# 02_MonitorStage_v1.net
KiCad netlist of a schematic drawn in EAGLE
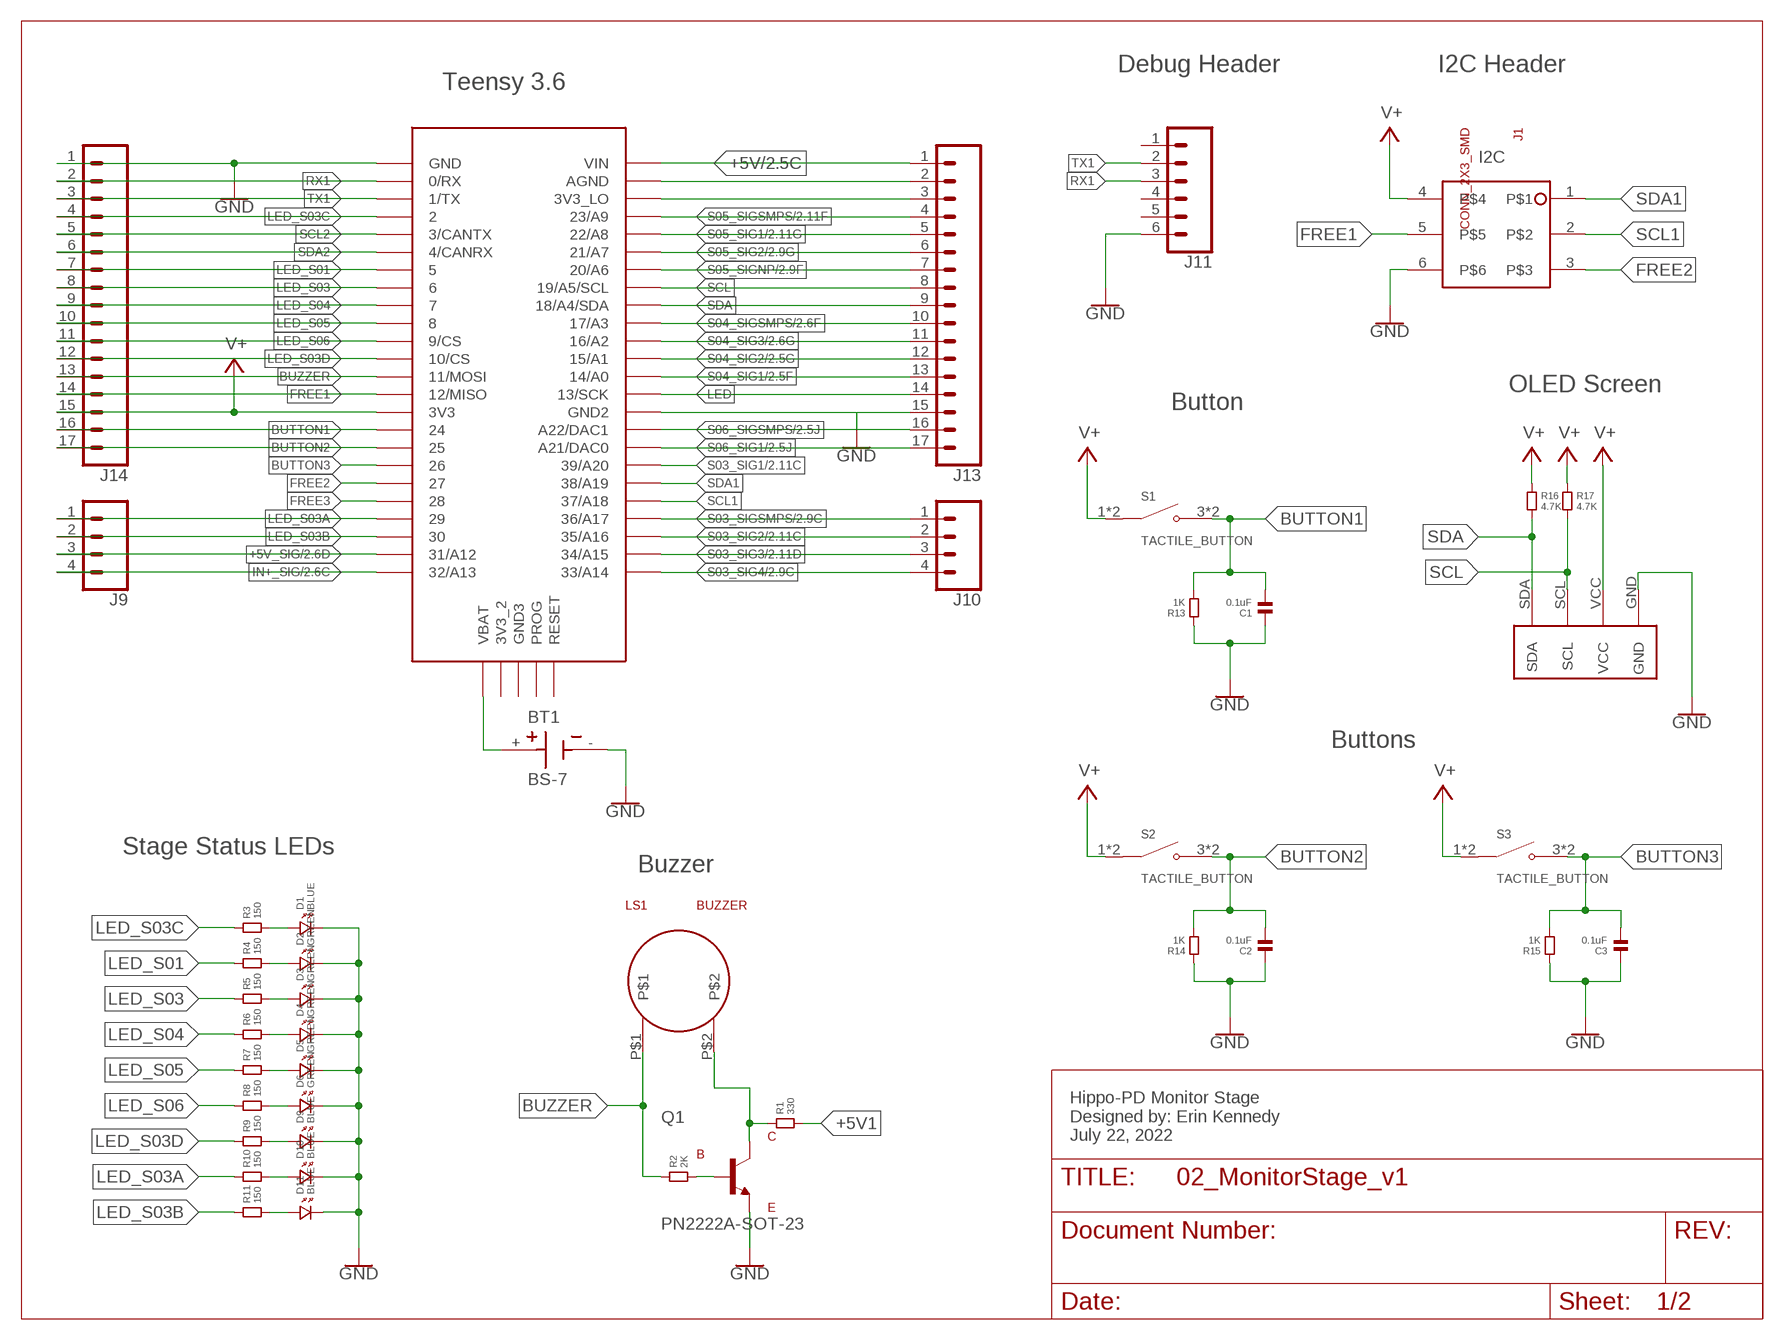
[diagram p0: schematic, sheet 1]
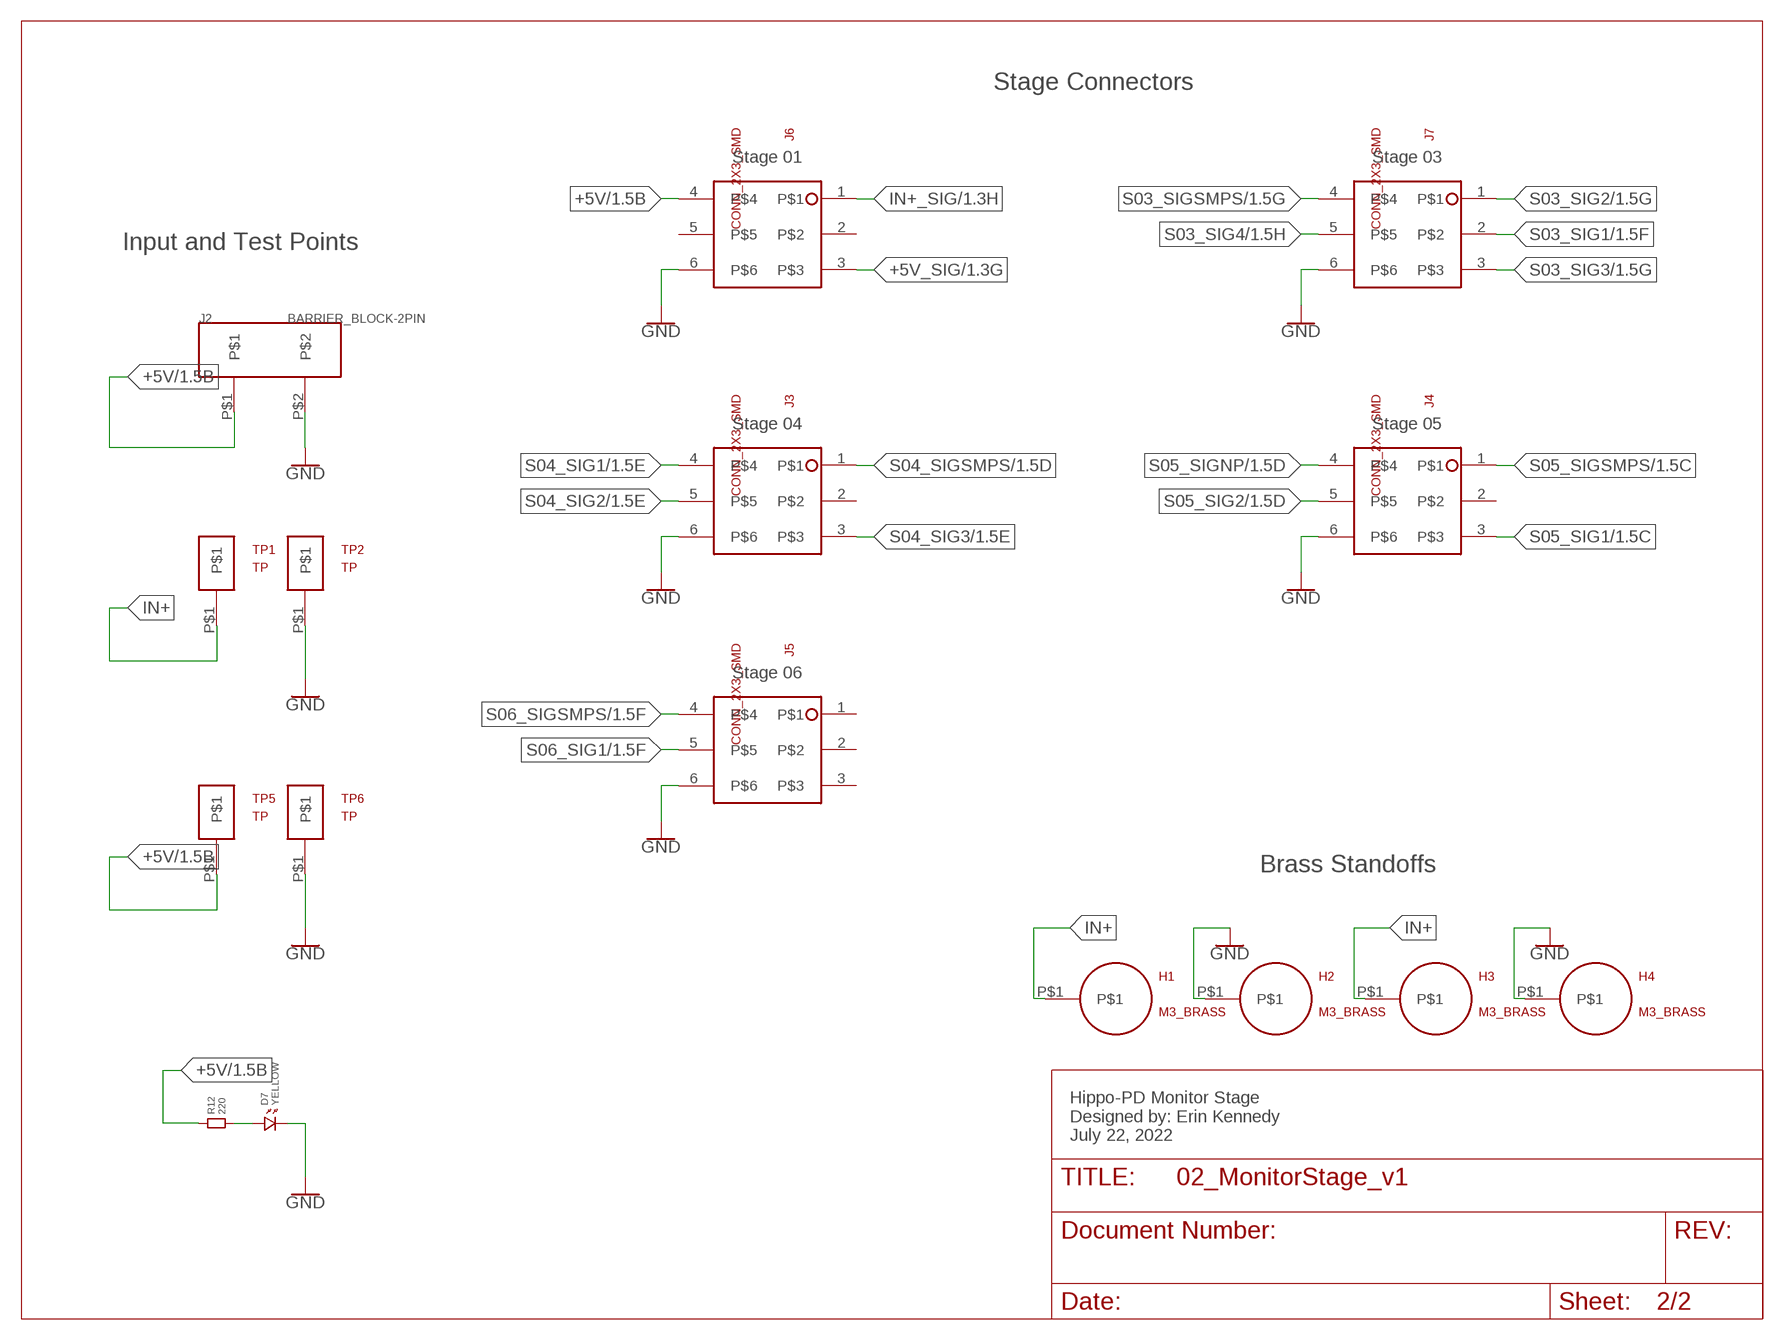
[diagram p1: schematic, sheet 2]

(export (version "E")
  (design (tool "Eeschema 10.0.6"))
  (components
    (comp (ref "BT1")
      (value "BS-7")
      (footprint "eagle-import:BAT_BS-7")
      (fields (field (name "MF") "MPD (Memory"))
      (libsource (lib "eagle-import") (part "BS-7"))
    )
    (comp (ref "C1")
      (value "0.1uF")
      (footprint "eagle-import:1206")
      (libsource (lib "eagle-import") (part "CAPACITOR.1206"))
    )
    (comp (ref "C2")
      (value "0.1uF")
      (footprint "eagle-import:1206")
      (libsource (lib "eagle-import") (part "CAPACITOR.1206"))
    )
    (comp (ref "C3")
      (value "0.1uF")
      (footprint "eagle-import:1206")
      (libsource (lib "eagle-import") (part "CAPACITOR.1206"))
    )
    (comp (ref "D1")
      (value "BLUE")
      (footprint "eagle-import:1206.LED")
      (libsource (lib "eagle-import") (part "LED.1206"))
    )
    (comp (ref "D2")
      (value "GREEN")
      (footprint "eagle-import:1206.LED")
      (libsource (lib "eagle-import") (part "LED.1206"))
    )
    (comp (ref "D3")
      (value "GREEN")
      (footprint "eagle-import:1206.LED")
      (libsource (lib "eagle-import") (part "LED.1206"))
    )
    (comp (ref "D4")
      (value "GREEN")
      (footprint "eagle-import:1206.LED")
      (libsource (lib "eagle-import") (part "LED.1206"))
    )
    (comp (ref "D5")
      (value "GREEN")
      (footprint "eagle-import:1206.LED")
      (libsource (lib "eagle-import") (part "LED.1206"))
    )
    (comp (ref "D6")
      (value "GREEN")
      (footprint "eagle-import:1206.LED")
      (libsource (lib "eagle-import") (part "LED.1206"))
    )
    (comp (ref "D9")
      (value "BLUE")
      (footprint "eagle-import:1206.LED")
      (libsource (lib "eagle-import") (part "LED.1206"))
    )
    (comp (ref "D10")
      (value "BLUE")
      (footprint "eagle-import:1206.LED")
      (libsource (lib "eagle-import") (part "LED.1206"))
    )
    (comp (ref "D11")
      (value "BLUE")
      (footprint "eagle-import:1206.LED")
      (libsource (lib "eagle-import") (part "LED.1206"))
    )
    (comp (ref "J1")
      (value "CONN_2X3_SMD")
      (footprint "eagle-import:2X3_SMD_CONNECTOR")
      (libsource (lib "eagle-import") (part "CONN_2X3_SMD"))
    )
    (comp (ref "J9")
      (value "CONN_04")
      (footprint "eagle-import:1X04")
      (libsource (lib "eagle-import") (part "CONN_04"))
    )
    (comp (ref "J10")
      (value "CONN_04")
      (footprint "eagle-import:1X04")
      (libsource (lib "eagle-import") (part "CONN_04"))
    )
    (comp (ref "J11")
      (value "CONN_06")
      (footprint "eagle-import:1X06-SMD_RA_MALE_NO_HOLES")
      (libsource (lib "eagle-import") (part "CONN_06"))
    )
    (comp (ref "J13")
      (value "CONN_17")
      (footprint "eagle-import:1X17")
      (libsource (lib "eagle-import") (part "CONN_17"))
    )
    (comp (ref "J14")
      (value "CONN_17")
      (footprint "eagle-import:1X17")
      (libsource (lib "eagle-import") (part "CONN_17"))
    )
    (comp (ref "LS1")
      (value "BUZZER")
      (footprint "eagle-import:BUZZER")
      (libsource (lib "eagle-import") (part "BUZZER"))
    )
    (comp (ref "Q1")
      (value "PN2222A-SOT-23")
      (footprint "eagle-import:PN2222A-SOT-23")
      (fields (field (name "MF") "Nexperia USA") (field (name "MP") "MMBT3904,215"))
      (libsource (lib "eagle-import") (part "PN2222A-SOT-23"))
    )
    (comp (ref "R1")
      (value "330")
      (footprint "eagle-import:1206")
      (libsource (lib "eagle-import") (part "RESISTOR.1206"))
    )
    (comp (ref "R2")
      (value "2K")
      (footprint "eagle-import:1206")
      (libsource (lib "eagle-import") (part "RESISTOR.1206"))
    )
    (comp (ref "R3")
      (value "150")
      (footprint "eagle-import:1206")
      (libsource (lib "eagle-import") (part "RESISTOR.1206"))
    )
    (comp (ref "R4")
      (value "150")
      (footprint "eagle-import:1206")
      (libsource (lib "eagle-import") (part "RESISTOR.1206"))
    )
    (comp (ref "R5")
      (value "150")
      (footprint "eagle-import:1206")
      (libsource (lib "eagle-import") (part "RESISTOR.1206"))
    )
    (comp (ref "R6")
      (value "150")
      (footprint "eagle-import:1206")
      (libsource (lib "eagle-import") (part "RESISTOR.1206"))
    )
    (comp (ref "R7")
      (value "150")
      (footprint "eagle-import:1206")
      (libsource (lib "eagle-import") (part "RESISTOR.1206"))
    )
    (comp (ref "R8")
      (value "150")
      (footprint "eagle-import:1206")
      (libsource (lib "eagle-import") (part "RESISTOR.1206"))
    )
    (comp (ref "R9")
      (value "150")
      (footprint "eagle-import:1206")
      (libsource (lib "eagle-import") (part "RESISTOR.1206"))
    )
    (comp (ref "R10")
      (value "150")
      (footprint "eagle-import:1206")
      (libsource (lib "eagle-import") (part "RESISTOR.1206"))
    )
    (comp (ref "R11")
      (value "150")
      (footprint "eagle-import:1206")
      (libsource (lib "eagle-import") (part "RESISTOR.1206"))
    )
    (comp (ref "R13")
      (value "1K")
      (footprint "eagle-import:1206")
      (libsource (lib "eagle-import") (part "RESISTOR.1206"))
    )
    (comp (ref "R14")
      (value "1K")
      (footprint "eagle-import:1206")
      (libsource (lib "eagle-import") (part "RESISTOR.1206"))
    )
    (comp (ref "R15")
      (value "1K")
      (footprint "eagle-import:1206")
      (libsource (lib "eagle-import") (part "RESISTOR.1206"))
    )
    (comp (ref "R16")
      (value "4.7K")
      (footprint "eagle-import:1206")
      (libsource (lib "eagle-import") (part "RESISTOR.1206"))
    )
    (comp (ref "R17")
      (value "4.7K")
      (footprint "eagle-import:1206")
      (libsource (lib "eagle-import") (part "RESISTOR.1206"))
    )
    (comp (ref "S1")
      (value "TACTILE_BUTTON")
      (footprint "eagle-import:TACTILE_BUTTON")
      (fields (field (name "MF") "C&K") (field (name "MP") "PTS526 SM08 SMTR2 LFS"))
      (libsource (lib "eagle-import") (part "TACTILE_BUTTON"))
    )
    (comp (ref "S2")
      (value "TACTILE_BUTTON")
      (footprint "eagle-import:TACTILE_BUTTON")
      (fields (field (name "MF") "C&K") (field (name "MP") "PTS526 SM08 SMTR2 LFS"))
      (libsource (lib "eagle-import") (part "TACTILE_BUTTON"))
    )
    (comp (ref "S3")
      (value "TACTILE_BUTTON")
      (footprint "eagle-import:TACTILE_BUTTON")
      (fields (field (name "MF") "C&K") (field (name "MP") "PTS526 SM08 SMTR2 LFS"))
      (libsource (lib "eagle-import") (part "TACTILE_BUTTON"))
    )
    (comp (ref "U1")
      (value "TEENSY_3.5/3.6")
      (footprint "eagle-import:TEENSY_3.5_3.6")
      (libsource (lib "eagle-import") (part "TEENSY_3.5/3.6"))
    )
    (comp (ref "U2")
      (value "TINYSCREEN")
      (footprint "eagle-import:TINYSCREEN")
      (libsource (lib "eagle-import") (part "TINYSCREEN"))
    )
    (comp (ref "D7")
      (value "YELLOW")
      (footprint "eagle-import:1206.LED")
      (libsource (lib "eagle-import") (part "LED.1206"))
    )
    (comp (ref "H1")
      (value "M3_BRASS")
      (footprint "eagle-import:M3_BRASS")
      (libsource (lib "eagle-import") (part "M3_BRASS"))
    )
    (comp (ref "H2")
      (value "M3_BRASS")
      (footprint "eagle-import:M3_BRASS")
      (libsource (lib "eagle-import") (part "M3_BRASS"))
    )
    (comp (ref "H3")
      (value "M3_BRASS")
      (footprint "eagle-import:M3_BRASS")
      (libsource (lib "eagle-import") (part "M3_BRASS"))
    )
    (comp (ref "H4")
      (value "M3_BRASS")
      (footprint "eagle-import:M3_BRASS")
      (libsource (lib "eagle-import") (part "M3_BRASS"))
    )
    (comp (ref "J2")
      (value "BARRIER_BLOCK-2PIN")
      (footprint "eagle-import:BARRIERBLOCK-2PIN")
      (libsource (lib "eagle-import") (part "BARRIER_BLOCK-2PIN"))
    )
    (comp (ref "J3")
      (value "CONN_2X3_SMD")
      (footprint "eagle-import:2X3_SMD_CONNECTOR")
      (libsource (lib "eagle-import") (part "CONN_2X3_SMD"))
    )
    (comp (ref "J4")
      (value "CONN_2X3_SMD")
      (footprint "eagle-import:2X3_SMD_CONNECTOR")
      (libsource (lib "eagle-import") (part "CONN_2X3_SMD"))
    )
    (comp (ref "J5")
      (value "CONN_2X3_SMD")
      (footprint "eagle-import:2X3_SMD_CONNECTOR")
      (libsource (lib "eagle-import") (part "CONN_2X3_SMD"))
    )
    (comp (ref "J6")
      (value "CONN_2X3_SMD")
      (footprint "eagle-import:2X3_SMD_CONNECTOR")
      (libsource (lib "eagle-import") (part "CONN_2X3_SMD"))
    )
    (comp (ref "J7")
      (value "CONN_2X3_SMD")
      (footprint "eagle-import:2X3_SMD_CONNECTOR")
      (libsource (lib "eagle-import") (part "CONN_2X3_SMD"))
    )
    (comp (ref "R12")
      (value "220")
      (footprint "eagle-import:1206")
      (libsource (lib "eagle-import") (part "RESISTOR.1206"))
    )
    (comp (ref "TP1") (value "TP") (footprint "eagle-import:TP") (libsource (lib "eagle-import") (part "TP")))
    (comp (ref "TP2") (value "TP") (footprint "eagle-import:TP") (libsource (lib "eagle-import") (part "TP")))
    (comp (ref "TP5") (value "TP") (footprint "eagle-import:TP") (libsource (lib "eagle-import") (part "TP")))
    (comp (ref "TP6") (value "TP") (footprint "eagle-import:TP") (libsource (lib "eagle-import") (part "TP")))
  )
  (nets
    (net (code "1") (name "+5V") (class "Default")
      (node (ref "J13") (pin "1") (pinfunction "1_1") (pintype "passive"))
      (node (ref "J2") (pin "P$1") (pinfunction "P$1_P$1") (pintype "bidirectional"))
      (node (ref "J6") (pin "4") (pinfunction "P$4_4") (pintype "bidirectional"))
      (node (ref "R12") (pin "1") (pinfunction "1_1") (pintype "bidirectional"))
      (node (ref "TP5") (pin "P$1") (pinfunction "P$1_P$1") (pintype "bidirectional"))
      (node (ref "U1") (pin "VIN") (pinfunction "VIN_VIN") (pintype "bidirectional"))
    )
    (net (code "2") (name "+5V1") (class "Default")
      (node (ref "R1") (pin "2") (pinfunction "2_2") (pintype "bidirectional"))
    )
    (net (code "3") (name "+5V_SIG") (class "Default")
      (node (ref "J6") (pin "3") (pinfunction "P$3_3") (pintype "bidirectional"))
      (node (ref "J9") (pin "3") (pinfunction "3_3") (pintype "passive"))
      (node (ref "U1") (pin "31/A12") (pinfunction "31/A12_31/A12") (pintype "bidirectional"))
    )
    (net (code "4") (name "BUTTON1") (class "Default")
      (node (ref "C1") (pin "2") (pinfunction "2_2") (pintype "bidirectional"))
      (node (ref "J14") (pin "16") (pinfunction "16_16") (pintype "passive"))
      (node (ref "R13") (pin "2") (pinfunction "2_2") (pintype "bidirectional"))
      (node (ref "S1") (pin "3") (pinfunction "NO_3") (pintype "passive"))
      (node (ref "S1") (pin "4") (pinfunction "NO_4") (pintype "passive"))
      (node (ref "U1") (pin "24") (pinfunction "24_24") (pintype "bidirectional"))
    )
    (net (code "5") (name "BUTTON2") (class "Default")
      (node (ref "C2") (pin "2") (pinfunction "2_2") (pintype "bidirectional"))
      (node (ref "J14") (pin "17") (pinfunction "17_17") (pintype "passive"))
      (node (ref "R14") (pin "2") (pinfunction "2_2") (pintype "bidirectional"))
      (node (ref "S2") (pin "3") (pinfunction "NO_3") (pintype "passive"))
      (node (ref "S2") (pin "4") (pinfunction "NO_4") (pintype "passive"))
      (node (ref "U1") (pin "25") (pinfunction "25_25") (pintype "bidirectional"))
    )
    (net (code "6") (name "BUTTON3") (class "Default")
      (node (ref "C3") (pin "2") (pinfunction "2_2") (pintype "bidirectional"))
      (node (ref "R15") (pin "2") (pinfunction "2_2") (pintype "bidirectional"))
      (node (ref "S3") (pin "3") (pinfunction "NO_3") (pintype "passive"))
      (node (ref "S3") (pin "4") (pinfunction "NO_4") (pintype "passive"))
      (node (ref "U1") (pin "26") (pinfunction "26_26") (pintype "bidirectional"))
    )
    (net (code "7") (name "BUZZER") (class "Default")
      (node (ref "J14") (pin "13") (pinfunction "13_13") (pintype "passive"))
      (node (ref "LS1") (pin "P$1") (pinfunction "P$1_P$1") (pintype "bidirectional"))
      (node (ref "R2") (pin "1") (pinfunction "1_1") (pintype "bidirectional"))
      (node (ref "U1") (pin "11/MOSI") (pinfunction "11/MOSI_11/MOSI") (pintype "bidirectional"))
    )
    (net (code "8") (name "FREE1") (class "Default")
      (node (ref "J1") (pin "5") (pinfunction "P$5_5") (pintype "bidirectional"))
      (node (ref "J14") (pin "14") (pinfunction "14_14") (pintype "passive"))
      (node (ref "U1") (pin "12/MISO") (pinfunction "12/MISO_12/MISO") (pintype "bidirectional"))
    )
    (net (code "9") (name "FREE2") (class "Default")
      (node (ref "J1") (pin "3") (pinfunction "P$3_3") (pintype "bidirectional"))
      (node (ref "U1") (pin "27") (pinfunction "27_27") (pintype "bidirectional"))
    )
    (net (code "10") (name "FREE3") (class "Default")
      (node (ref "U1") (pin "28") (pinfunction "28_28") (pintype "bidirectional"))
    )
    (net (code "11") (name "GND") (class "Default")
      (node (ref "BT1") (pin "-") (pinfunction "-_-") (pintype "passive"))
      (node (ref "C1") (pin "1") (pinfunction "1_1") (pintype "bidirectional"))
      (node (ref "C2") (pin "1") (pinfunction "1_1") (pintype "bidirectional"))
      (node (ref "C3") (pin "1") (pinfunction "1_1") (pintype "bidirectional"))
      (node (ref "D1") (pin "P$2") (pinfunction "2_P$2") (pintype "bidirectional"))
      (node (ref "D10") (pin "P$2") (pinfunction "2_P$2") (pintype "bidirectional"))
      (node (ref "D11") (pin "P$2") (pinfunction "2_P$2") (pintype "bidirectional"))
      (node (ref "D2") (pin "P$2") (pinfunction "2_P$2") (pintype "bidirectional"))
      (node (ref "D3") (pin "P$2") (pinfunction "2_P$2") (pintype "bidirectional"))
      (node (ref "D4") (pin "P$2") (pinfunction "2_P$2") (pintype "bidirectional"))
      (node (ref "D5") (pin "P$2") (pinfunction "2_P$2") (pintype "bidirectional"))
      (node (ref "D6") (pin "P$2") (pinfunction "2_P$2") (pintype "bidirectional"))
      (node (ref "D7") (pin "P$2") (pinfunction "2_P$2") (pintype "bidirectional"))
      (node (ref "D9") (pin "P$2") (pinfunction "2_P$2") (pintype "bidirectional"))
      (node (ref "H2") (pin "P$1") (pinfunction "P$1_P$1") (pintype "bidirectional"))
      (node (ref "H4") (pin "P$1") (pinfunction "P$1_P$1") (pintype "bidirectional"))
      (node (ref "J1") (pin "6") (pinfunction "P$6_6") (pintype "bidirectional"))
      (node (ref "J11") (pin "6") (pinfunction "6_6") (pintype "passive"))
      (node (ref "J13") (pin "15") (pinfunction "15_15") (pintype "passive"))
      (node (ref "J14") (pin "1") (pinfunction "1_1") (pintype "passive"))
      (node (ref "J2") (pin "P$2") (pinfunction "P$2_P$2") (pintype "bidirectional"))
      (node (ref "J3") (pin "6") (pinfunction "P$6_6") (pintype "bidirectional"))
      (node (ref "J4") (pin "6") (pinfunction "P$6_6") (pintype "bidirectional"))
      (node (ref "J5") (pin "6") (pinfunction "P$6_6") (pintype "bidirectional"))
      (node (ref "J6") (pin "6") (pinfunction "P$6_6") (pintype "bidirectional"))
      (node (ref "J7") (pin "6") (pinfunction "P$6_6") (pintype "bidirectional"))
      (node (ref "Q1") (pin "EMITTER") (pinfunction "EMITTER_EMITTER") (pintype "passive"))
      (node (ref "R13") (pin "1") (pinfunction "1_1") (pintype "bidirectional"))
      (node (ref "R14") (pin "1") (pinfunction "1_1") (pintype "bidirectional"))
      (node (ref "R15") (pin "1") (pinfunction "1_1") (pintype "bidirectional"))
      (node (ref "TP2") (pin "P$1") (pinfunction "P$1_P$1") (pintype "bidirectional"))
      (node (ref "TP6") (pin "P$1") (pinfunction "P$1_P$1") (pintype "bidirectional"))
      (node (ref "U1") (pin "GND") (pinfunction "GND_GND") (pintype "bidirectional"))
      (node (ref "U1") (pin "GND2") (pinfunction "GND2_GND2") (pintype "bidirectional"))
      (node (ref "U2") (pin "GND") (pinfunction "GND_GND") (pintype "bidirectional"))
    )
    (net (code "12") (name "IN+") (class "Default")
      (node (ref "H1") (pin "P$1") (pinfunction "P$1_P$1") (pintype "bidirectional"))
      (node (ref "H3") (pin "P$1") (pinfunction "P$1_P$1") (pintype "bidirectional"))
      (node (ref "TP1") (pin "P$1") (pinfunction "P$1_P$1") (pintype "bidirectional"))
    )
    (net (code "13") (name "IN+_SIG") (class "Default")
      (node (ref "J6") (pin "1") (pinfunction "P$1_1") (pintype "bidirectional"))
      (node (ref "J9") (pin "4") (pinfunction "4_4") (pintype "passive"))
      (node (ref "U1") (pin "32/A13") (pinfunction "32/A13_32/A13") (pintype "bidirectional"))
    )
    (net (code "14") (name "LED") (class "Default")
      (node (ref "J13") (pin "14") (pinfunction "14_14") (pintype "passive"))
      (node (ref "U1") (pin "13/SCK") (pinfunction "13/SCK_13/SCK") (pintype "bidirectional"))
    )
    (net (code "15") (name "LED_S01") (class "Default")
      (node (ref "J14") (pin "7") (pinfunction "7_7") (pintype "passive"))
      (node (ref "R4") (pin "1") (pinfunction "1_1") (pintype "bidirectional"))
      (node (ref "U1") (pin "5") (pinfunction "5_5") (pintype "bidirectional"))
    )
    (net (code "16") (name "LED_S03") (class "Default")
      (node (ref "J14") (pin "8") (pinfunction "8_8") (pintype "passive"))
      (node (ref "R5") (pin "1") (pinfunction "1_1") (pintype "bidirectional"))
      (node (ref "U1") (pin "6") (pinfunction "6_6") (pintype "bidirectional"))
    )
    (net (code "17") (name "LED_S03A") (class "Default")
      (node (ref "J9") (pin "1") (pinfunction "1_1") (pintype "passive"))
      (node (ref "R10") (pin "1") (pinfunction "1_1") (pintype "bidirectional"))
      (node (ref "U1") (pin "29") (pinfunction "29_29") (pintype "bidirectional"))
    )
    (net (code "18") (name "LED_S03B") (class "Default")
      (node (ref "J9") (pin "2") (pinfunction "2_2") (pintype "passive"))
      (node (ref "R11") (pin "1") (pinfunction "1_1") (pintype "bidirectional"))
      (node (ref "U1") (pin "30") (pinfunction "30_30") (pintype "bidirectional"))
    )
    (net (code "19") (name "LED_S03C") (class "Default")
      (node (ref "J14") (pin "4") (pinfunction "4_4") (pintype "passive"))
      (node (ref "R3") (pin "1") (pinfunction "1_1") (pintype "bidirectional"))
      (node (ref "U1") (pin "2") (pinfunction "2_2") (pintype "bidirectional"))
    )
    (net (code "20") (name "LED_S03D") (class "Default")
      (node (ref "J14") (pin "12") (pinfunction "12_12") (pintype "passive"))
      (node (ref "R9") (pin "1") (pinfunction "1_1") (pintype "bidirectional"))
      (node (ref "U1") (pin "10/CS") (pinfunction "10/CS_10/CS") (pintype "bidirectional"))
    )
    (net (code "21") (name "LED_S04") (class "Default")
      (node (ref "J14") (pin "9") (pinfunction "9_9") (pintype "passive"))
      (node (ref "R6") (pin "1") (pinfunction "1_1") (pintype "bidirectional"))
      (node (ref "U1") (pin "7") (pinfunction "7_7") (pintype "bidirectional"))
    )
    (net (code "22") (name "LED_S05") (class "Default")
      (node (ref "J14") (pin "10") (pinfunction "10_10") (pintype "passive"))
      (node (ref "R7") (pin "1") (pinfunction "1_1") (pintype "bidirectional"))
      (node (ref "U1") (pin "8") (pinfunction "8_8") (pintype "bidirectional"))
    )
    (net (code "23") (name "LED_S06") (class "Default")
      (node (ref "J14") (pin "11") (pinfunction "11_11") (pintype "passive"))
      (node (ref "R8") (pin "1") (pinfunction "1_1") (pintype "bidirectional"))
      (node (ref "U1") (pin "9/CS") (pinfunction "9/CS_9/CS") (pintype "bidirectional"))
    )
    (net (code "24") (name "Net-(BT1-Pad+)") (class "Default")
      (node (ref "BT1") (pin "+") (pinfunction "+_+") (pintype "passive"))
      (node (ref "U1") (pin "VBAT") (pinfunction "VBAT_VBAT") (pintype "bidirectional"))
    )
    (net (code "25") (name "Net-(D1-1)") (class "Default")
      (node (ref "D1") (pin "P$1") (pinfunction "1_P$1") (pintype "bidirectional"))
      (node (ref "R3") (pin "2") (pinfunction "2_2") (pintype "bidirectional"))
    )
    (net (code "26") (name "Net-(D2-1)") (class "Default")
      (node (ref "D2") (pin "P$1") (pinfunction "1_P$1") (pintype "bidirectional"))
      (node (ref "R4") (pin "2") (pinfunction "2_2") (pintype "bidirectional"))
    )
    (net (code "27") (name "Net-(D3-1)") (class "Default")
      (node (ref "D3") (pin "P$1") (pinfunction "1_P$1") (pintype "bidirectional"))
      (node (ref "R5") (pin "2") (pinfunction "2_2") (pintype "bidirectional"))
    )
    (net (code "28") (name "Net-(D4-1)") (class "Default")
      (node (ref "D4") (pin "P$1") (pinfunction "1_P$1") (pintype "bidirectional"))
      (node (ref "R6") (pin "2") (pinfunction "2_2") (pintype "bidirectional"))
    )
    (net (code "29") (name "Net-(D5-1)") (class "Default")
      (node (ref "D5") (pin "P$1") (pinfunction "1_P$1") (pintype "bidirectional"))
      (node (ref "R7") (pin "2") (pinfunction "2_2") (pintype "bidirectional"))
    )
    (net (code "30") (name "Net-(D6-1)") (class "Default")
      (node (ref "D6") (pin "P$1") (pinfunction "1_P$1") (pintype "bidirectional"))
      (node (ref "R8") (pin "2") (pinfunction "2_2") (pintype "bidirectional"))
    )
    (net (code "31") (name "Net-(D7-1)") (class "Default")
      (node (ref "D7") (pin "P$1") (pinfunction "1_P$1") (pintype "bidirectional"))
      (node (ref "R12") (pin "2") (pinfunction "2_2") (pintype "bidirectional"))
    )
    (net (code "32") (name "Net-(D9-1)") (class "Default")
      (node (ref "D9") (pin "P$1") (pinfunction "1_P$1") (pintype "bidirectional"))
      (node (ref "R9") (pin "2") (pinfunction "2_2") (pintype "bidirectional"))
    )
    (net (code "33") (name "Net-(D10-1)") (class "Default")
      (node (ref "D10") (pin "P$1") (pinfunction "1_P$1") (pintype "bidirectional"))
      (node (ref "R10") (pin "2") (pinfunction "2_2") (pintype "bidirectional"))
    )
    (net (code "34") (name "Net-(D11-1)") (class "Default")
      (node (ref "D11") (pin "P$1") (pinfunction "1_P$1") (pintype "bidirectional"))
      (node (ref "R11") (pin "2") (pinfunction "2_2") (pintype "bidirectional"))
    )
    (net (code "35") (name "Net-(J13-Pad2)") (class "Default")
      (node (ref "J13") (pin "2") (pinfunction "2_2") (pintype "passive"))
      (node (ref "U1") (pin "AGND") (pinfunction "AGND_AGND") (pintype "bidirectional"))
    )
    (net (code "36") (name "Net-(J13-Pad3)") (class "Default")
      (node (ref "J13") (pin "3") (pinfunction "3_3") (pintype "passive"))
      (node (ref "U1") (pin "3V3_LO") (pinfunction "3V3_LO_3V3_LO") (pintype "bidirectional"))
    )
    (net (code "37") (name "Net-(LS1-PadP$2)") (class "Default")
      (node (ref "LS1") (pin "P$2") (pinfunction "P$2_P$2") (pintype "bidirectional"))
      (node (ref "Q1") (pin "COLLECTOR") (pinfunction "COLLECTOR_COLLECTOR") (pintype "passive"))
      (node (ref "R1") (pin "1") (pinfunction "1_1") (pintype "bidirectional"))
    )
    (net (code "38") (name "Net-(Q1-PadBASE)") (class "Default")
      (node (ref "Q1") (pin "BASE") (pinfunction "BASE_BASE") (pintype "passive"))
      (node (ref "R2") (pin "2") (pinfunction "2_2") (pintype "bidirectional"))
    )
    (net (code "39") (name "RX1") (class "Default")
      (node (ref "J11") (pin "3") (pinfunction "3_3") (pintype "passive"))
      (node (ref "J14") (pin "2") (pinfunction "2_2") (pintype "passive"))
      (node (ref "U1") (pin "0/RX") (pinfunction "0/RX_0/RX") (pintype "bidirectional"))
    )
    (net (code "40") (name "S03_SIG1") (class "Default")
      (node (ref "J7") (pin "2") (pinfunction "P$2_2") (pintype "bidirectional"))
      (node (ref "U1") (pin "39/A20") (pinfunction "39/A20_39/A20") (pintype "bidirectional"))
    )
    (net (code "41") (name "S03_SIG2") (class "Default")
      (node (ref "J10") (pin "2") (pinfunction "2_2") (pintype "passive"))
      (node (ref "J7") (pin "1") (pinfunction "P$1_1") (pintype "bidirectional"))
      (node (ref "U1") (pin "35/A16") (pinfunction "35/A16_35/A16") (pintype "bidirectional"))
    )
    (net (code "42") (name "S03_SIG3") (class "Default")
      (node (ref "J10") (pin "3") (pinfunction "3_3") (pintype "passive"))
      (node (ref "J7") (pin "3") (pinfunction "P$3_3") (pintype "bidirectional"))
      (node (ref "U1") (pin "34/A15") (pinfunction "34/A15_34/A15") (pintype "bidirectional"))
    )
    (net (code "43") (name "S03_SIG4") (class "Default")
      (node (ref "J10") (pin "4") (pinfunction "4_4") (pintype "passive"))
      (node (ref "J7") (pin "5") (pinfunction "P$5_5") (pintype "bidirectional"))
      (node (ref "U1") (pin "33/A14") (pinfunction "33/A14_33/A14") (pintype "bidirectional"))
    )
    (net (code "44") (name "S03_SIGSMPS") (class "Default")
      (node (ref "J10") (pin "1") (pinfunction "1_1") (pintype "passive"))
      (node (ref "J7") (pin "4") (pinfunction "P$4_4") (pintype "bidirectional"))
      (node (ref "U1") (pin "36/A17") (pinfunction "36/A17_36/A17") (pintype "bidirectional"))
    )
    (net (code "45") (name "S04_SIG1") (class "Default")
      (node (ref "J13") (pin "13") (pinfunction "13_13") (pintype "passive"))
      (node (ref "J3") (pin "4") (pinfunction "P$4_4") (pintype "bidirectional"))
      (node (ref "U1") (pin "14/A0") (pinfunction "14/A0_14/A0") (pintype "bidirectional"))
    )
    (net (code "46") (name "S04_SIG2") (class "Default")
      (node (ref "J13") (pin "12") (pinfunction "12_12") (pintype "passive"))
      (node (ref "J3") (pin "5") (pinfunction "P$5_5") (pintype "bidirectional"))
      (node (ref "U1") (pin "15/A1") (pinfunction "15/A1_15/A1") (pintype "bidirectional"))
    )
    (net (code "47") (name "S04_SIG3") (class "Default")
      (node (ref "J13") (pin "11") (pinfunction "11_11") (pintype "passive"))
      (node (ref "J3") (pin "3") (pinfunction "P$3_3") (pintype "bidirectional"))
      (node (ref "U1") (pin "16/A2") (pinfunction "16/A2_16/A2") (pintype "bidirectional"))
    )
    (net (code "48") (name "S04_SIGSMPS") (class "Default")
      (node (ref "J13") (pin "10") (pinfunction "10_10") (pintype "passive"))
      (node (ref "J3") (pin "1") (pinfunction "P$1_1") (pintype "bidirectional"))
      (node (ref "U1") (pin "17/A3") (pinfunction "17/A3_17/A3") (pintype "bidirectional"))
    )
    (net (code "49") (name "S05_SIG1") (class "Default")
      (node (ref "J13") (pin "5") (pinfunction "5_5") (pintype "passive"))
      (node (ref "J4") (pin "3") (pinfunction "P$3_3") (pintype "bidirectional"))
      (node (ref "U1") (pin "22/A8") (pinfunction "22/A8_22/A8") (pintype "bidirectional"))
    )
    (net (code "50") (name "S05_SIG2") (class "Default")
      (node (ref "J13") (pin "6") (pinfunction "6_6") (pintype "passive"))
      (node (ref "J4") (pin "5") (pinfunction "P$5_5") (pintype "bidirectional"))
      (node (ref "U1") (pin "21/A7") (pinfunction "21/A7_21/A7") (pintype "bidirectional"))
    )
    (net (code "51") (name "S05_SIGNP") (class "Default")
      (node (ref "J13") (pin "7") (pinfunction "7_7") (pintype "passive"))
      (node (ref "J4") (pin "4") (pinfunction "P$4_4") (pintype "bidirectional"))
      (node (ref "U1") (pin "20/A6") (pinfunction "20/A6_20/A6") (pintype "bidirectional"))
    )
    (net (code "52") (name "S05_SIGSMPS") (class "Default")
      (node (ref "J13") (pin "4") (pinfunction "4_4") (pintype "passive"))
      (node (ref "J4") (pin "1") (pinfunction "P$1_1") (pintype "bidirectional"))
      (node (ref "U1") (pin "23/A9") (pinfunction "23/A9_23/A9") (pintype "bidirectional"))
    )
    (net (code "53") (name "S06_SIG1") (class "Default")
      (node (ref "J13") (pin "17") (pinfunction "17_17") (pintype "passive"))
      (node (ref "J5") (pin "5") (pinfunction "P$5_5") (pintype "bidirectional"))
      (node (ref "U1") (pin "21/DAC0") (pinfunction "A21/DAC0_21/DAC0") (pintype "bidirectional"))
    )
    (net (code "54") (name "S06_SIGSMPS") (class "Default")
      (node (ref "J13") (pin "16") (pinfunction "16_16") (pintype "passive"))
      (node (ref "J5") (pin "4") (pinfunction "P$4_4") (pintype "bidirectional"))
      (node (ref "U1") (pin "A22/DAC1") (pinfunction "A22/DAC1_A22/DAC1") (pintype "bidirectional"))
    )
    (net (code "55") (name "SCL") (class "Default")
      (node (ref "J13") (pin "8") (pinfunction "8_8") (pintype "passive"))
      (node (ref "R17") (pin "2") (pinfunction "2_2") (pintype "bidirectional"))
      (node (ref "U1") (pin "19/A5/SCL") (pinfunction "19/A5/SCL_19/A5/SCL") (pintype "bidirectional"))
      (node (ref "U2") (pin "SCL") (pinfunction "SCL_SCL") (pintype "bidirectional"))
    )
    (net (code "56") (name "SCL1") (class "Default")
      (node (ref "J1") (pin "2") (pinfunction "P$2_2") (pintype "bidirectional"))
      (node (ref "U1") (pin "37/A18") (pinfunction "37/A18_37/A18") (pintype "bidirectional"))
    )
    (net (code "57") (name "SCL2") (class "Default")
      (node (ref "J14") (pin "5") (pinfunction "5_5") (pintype "passive"))
      (node (ref "U1") (pin "3/CANTX") (pinfunction "3/CANTX_3/CANTX") (pintype "bidirectional"))
    )
    (net (code "58") (name "SDA") (class "Default")
      (node (ref "J13") (pin "9") (pinfunction "9_9") (pintype "passive"))
      (node (ref "R16") (pin "2") (pinfunction "2_2") (pintype "bidirectional"))
      (node (ref "U1") (pin "18/A4/SDA") (pinfunction "18/A4/SDA_18/A4/SDA") (pintype "bidirectional"))
      (node (ref "U2") (pin "SDA") (pinfunction "SDA_SDA") (pintype "bidirectional"))
    )
    (net (code "59") (name "SDA1") (class "Default")
      (node (ref "J1") (pin "1") (pinfunction "P$1_1") (pintype "bidirectional"))
      (node (ref "U1") (pin "38/A19") (pinfunction "38/A19_38/A19") (pintype "bidirectional"))
    )
    (net (code "60") (name "SDA2") (class "Default")
      (node (ref "J14") (pin "6") (pinfunction "6_6") (pintype "passive"))
      (node (ref "U1") (pin "4/CANRX") (pinfunction "4/CANRX_4/CANRX") (pintype "bidirectional"))
    )
    (net (code "61") (name "TX1") (class "Default")
      (node (ref "J11") (pin "2") (pinfunction "2_2") (pintype "passive"))
      (node (ref "J14") (pin "3") (pinfunction "3_3") (pintype "passive"))
      (node (ref "U1") (pin "1/TX") (pinfunction "1/TX_1/TX") (pintype "bidirectional"))
    )
    (net (code "62") (name "V+") (class "Default")
      (node (ref "J1") (pin "4") (pinfunction "P$4_4") (pintype "bidirectional"))
      (node (ref "J14") (pin "15") (pinfunction "15_15") (pintype "passive"))
      (node (ref "R16") (pin "1") (pinfunction "1_1") (pintype "bidirectional"))
      (node (ref "R17") (pin "1") (pinfunction "1_1") (pintype "bidirectional"))
      (node (ref "S1") (pin "1") (pinfunction "COM_1") (pintype "passive"))
      (node (ref "S1") (pin "2") (pinfunction "COM_2") (pintype "passive"))
      (node (ref "S2") (pin "1") (pinfunction "COM_1") (pintype "passive"))
      (node (ref "S2") (pin "2") (pinfunction "COM_2") (pintype "passive"))
      (node (ref "S3") (pin "1") (pinfunction "COM_1") (pintype "passive"))
      (node (ref "S3") (pin "2") (pinfunction "COM_2") (pintype "passive"))
      (node (ref "U1") (pin "3V3") (pinfunction "3V3_3V3") (pintype "bidirectional"))
      (node (ref "U2") (pin "VCC") (pinfunction "VCC_VCC") (pintype "bidirectional"))
    )
    (net (code "63") (name "unconnected-(J3-P$2-Pad2)") (class "Default")
      (node (ref "J3") (pin "2") (pinfunction "P$2_2") (pintype "bidirectional"))
    )
    (net (code "64") (name "unconnected-(J4-P$2-Pad2)") (class "Default")
      (node (ref "J4") (pin "2") (pinfunction "P$2_2") (pintype "bidirectional"))
    )
    (net (code "65") (name "unconnected-(J5-P$1-Pad1)") (class "Default")
      (node (ref "J5") (pin "1") (pinfunction "P$1_1") (pintype "bidirectional"))
    )
    (net (code "66") (name "unconnected-(J5-P$2-Pad2)") (class "Default")
      (node (ref "J5") (pin "2") (pinfunction "P$2_2") (pintype "bidirectional"))
    )
    (net (code "67") (name "unconnected-(J5-P$3-Pad3)") (class "Default")
      (node (ref "J5") (pin "3") (pinfunction "P$3_3") (pintype "bidirectional"))
    )
    (net (code "68") (name "unconnected-(J6-P$2-Pad2)") (class "Default")
      (node (ref "J6") (pin "2") (pinfunction "P$2_2") (pintype "bidirectional"))
    )
    (net (code "69") (name "unconnected-(J6-P$5-Pad5)") (class "Default")
      (node (ref "J6") (pin "5") (pinfunction "P$5_5") (pintype "bidirectional"))
    )
    (net (code "70") (name "unconnected-(J11-Pad1)") (class "Default")
      (node (ref "J11") (pin "1") (pinfunction "1_1") (pintype "passive"))
    )
    (net (code "71") (name "unconnected-(J11-Pad4)") (class "Default")
      (node (ref "J11") (pin "4") (pinfunction "4_4") (pintype "passive"))
    )
    (net (code "72") (name "unconnected-(J11-Pad5)") (class "Default")
      (node (ref "J11") (pin "5") (pinfunction "5_5") (pintype "passive"))
    )
    (net (code "73") (name "unconnected-(U1-Pad3V3_2)") (class "Default")
      (node (ref "U1") (pin "3V3_2") (pinfunction "3V3_2_3V3_2") (pintype "bidirectional"))
    )
    (net (code "74") (name "unconnected-(U1-PadGND3)") (class "Default")
      (node (ref "U1") (pin "GND3") (pinfunction "GND3_GND3") (pintype "bidirectional"))
    )
    (net (code "75") (name "unconnected-(U1-PadPROG)") (class "Default")
      (node (ref "U1") (pin "PROG") (pinfunction "PROG_PROG") (pintype "bidirectional"))
    )
    (net (code "76") (name "unconnected-(U1-PadRESET)") (class "Default")
      (node (ref "U1") (pin "RESET") (pinfunction "RESET_RESET") (pintype "bidirectional"))
    )
  )
)
